# receiver.net
KiCad netlist of a schematic drawn in EAGLE
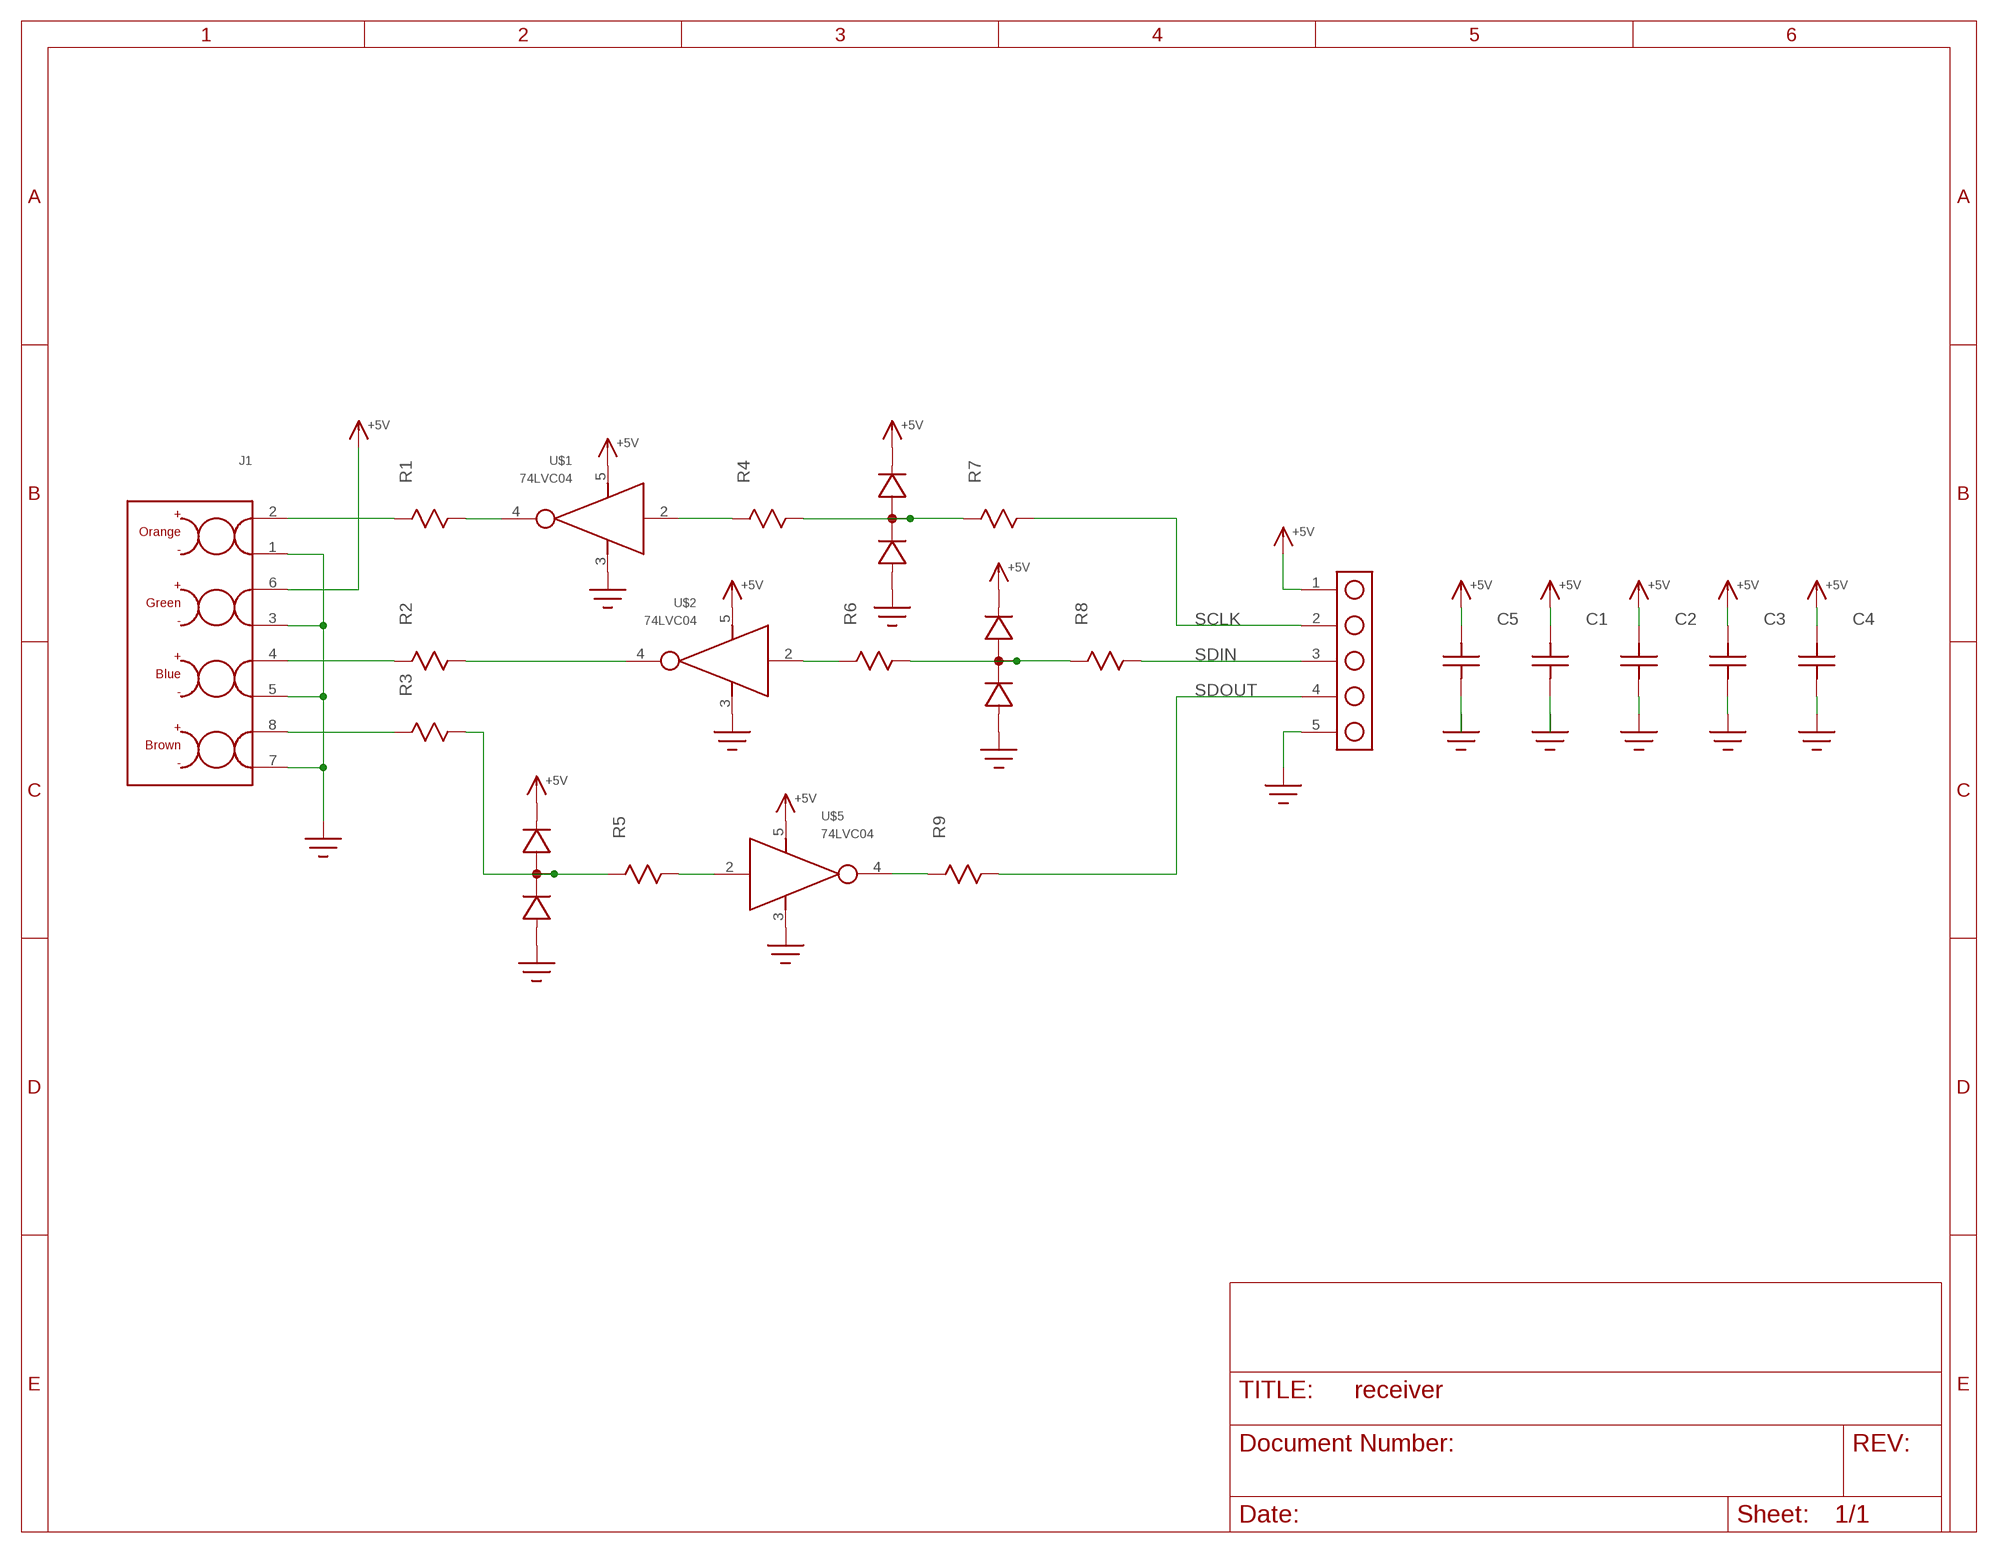
[diagram p0: schematic, sheet 1]

(export (version "E")
  (design (tool "Eeschema 10.0.6"))
  (components
    (comp (ref "C1")
      (value "C1206")
      (footprint "eagle-import:1206")
      (libsource (lib "eagle-import") (part "C1206"))
    )
    (comp (ref "C2")
      (value "C0805")
      (footprint "eagle-import:0805")
      (libsource (lib "eagle-import") (part "C0805"))
    )
    (comp (ref "C3")
      (value "C0805")
      (footprint "eagle-import:0805")
      (libsource (lib "eagle-import") (part "C0805"))
    )
    (comp (ref "C4")
      (value "C0805")
      (footprint "eagle-import:0805")
      (libsource (lib "eagle-import") (part "C0805"))
    )
    (comp (ref "C5")
      (value "C1206")
      (footprint "eagle-import:1206")
      (libsource (lib "eagle-import") (part "C1206"))
    )
    (comp (ref "J1")
      (value "RJ45")
      (footprint "eagle-import:RJ45_KEYSTONE_949")
      (libsource (lib "eagle-import") (part "RJ45"))
    )
    (comp (ref "J2")
      (value "HEADER_5PIN")
      (footprint "eagle-import:HEADER_5PIN")
      (libsource (lib "eagle-import") (part "HEADER_5PIN"))
    )
    (comp (ref "R1")
      (value "R0805")
      (footprint "eagle-import:R0805")
      (libsource (lib "eagle-import") (part "R0805"))
    )
    (comp (ref "R2")
      (value "R0805")
      (footprint "eagle-import:R0805")
      (libsource (lib "eagle-import") (part "R0805"))
    )
    (comp (ref "R3")
      (value "R0805")
      (footprint "eagle-import:R0805")
      (libsource (lib "eagle-import") (part "R0805"))
    )
    (comp (ref "R4")
      (value "R0805")
      (footprint "eagle-import:R0805")
      (libsource (lib "eagle-import") (part "R0805"))
    )
    (comp (ref "R5")
      (value "R0805")
      (footprint "eagle-import:R0805")
      (libsource (lib "eagle-import") (part "R0805"))
    )
    (comp (ref "R6")
      (value "R0805")
      (footprint "eagle-import:R0805")
      (libsource (lib "eagle-import") (part "R0805"))
    )
    (comp (ref "R7")
      (value "R0805")
      (footprint "eagle-import:R0805")
      (libsource (lib "eagle-import") (part "R0805"))
    )
    (comp (ref "R8")
      (value "R0805")
      (footprint "eagle-import:R0805")
      (libsource (lib "eagle-import") (part "R0805"))
    )
    (comp (ref "R9")
      (value "R0805")
      (footprint "eagle-import:R0805")
      (libsource (lib "eagle-import") (part "R0805"))
    )
    (comp (ref "U$1")
      (value "74LVC04")
      (footprint "eagle-import:SOT23-5")
      (libsource (lib "eagle-import") (part "74LVC04"))
    )
    (comp (ref "U$2")
      (value "74LVC04")
      (footprint "eagle-import:SOT23-5")
      (libsource (lib "eagle-import") (part "74LVC04"))
    )
    (comp (ref "U$5")
      (value "74LVC04")
      (footprint "eagle-import:SOT23-5")
      (libsource (lib "eagle-import") (part "74LVC04"))
    )
    (comp (ref "U$12")
      (value "MMBD7000L")
      (footprint "eagle-import:SOT-23")
      (libsource (lib "eagle-import") (part "MMBD7000L"))
    )
    (comp (ref "U$13")
      (value "MMBD7000L")
      (footprint "eagle-import:SOT-23")
      (libsource (lib "eagle-import") (part "MMBD7000L"))
    )
    (comp (ref "U$14")
      (value "MMBD7000L")
      (footprint "eagle-import:SOT-23")
      (libsource (lib "eagle-import") (part "MMBD7000L"))
    )
  )
  (nets
    (net (code "1") (name "+5V") (class "Default")
      (node (ref "C1") (pin "P$2") (pinfunction "P$2_P$2") (pintype "bidirectional"))
      (node (ref "C2") (pin "P$2") (pinfunction "P$2_P$2") (pintype "bidirectional"))
      (node (ref "C3") (pin "P$2") (pinfunction "P$2_P$2") (pintype "bidirectional"))
      (node (ref "C4") (pin "P$2") (pinfunction "P$2_P$2") (pintype "bidirectional"))
      (node (ref "C5") (pin "P$2") (pinfunction "P$2_P$2") (pintype "bidirectional"))
      (node (ref "J1") (pin "6") (pinfunction "6_6") (pintype "bidirectional"))
      (node (ref "J2") (pin "1") (pinfunction "1_1") (pintype "bidirectional"))
      (node (ref "U$1") (pin "5") (pinfunction "VCC_5") (pintype "bidirectional"))
      (node (ref "U$12") (pin "2") (pinfunction "CATHODE_2") (pintype "bidirectional"))
      (node (ref "U$13") (pin "2") (pinfunction "CATHODE_2") (pintype "bidirectional"))
      (node (ref "U$14") (pin "2") (pinfunction "CATHODE_2") (pintype "bidirectional"))
      (node (ref "U$2") (pin "5") (pinfunction "VCC_5") (pintype "bidirectional"))
      (node (ref "U$5") (pin "5") (pinfunction "VCC_5") (pintype "bidirectional"))
    )
    (net (code "2") (name "/SCLK") (class "Default")
      (node (ref "J2") (pin "2") (pinfunction "2_2") (pintype "bidirectional"))
      (node (ref "R7") (pin "P$2") (pinfunction "P$4_P$2") (pintype "bidirectional"))
    )
    (net (code "3") (name "/SDIN") (class "Default")
      (node (ref "J2") (pin "3") (pinfunction "3_3") (pintype "bidirectional"))
      (node (ref "R8") (pin "P$2") (pinfunction "P$4_P$2") (pintype "bidirectional"))
    )
    (net (code "4") (name "/SDOUT") (class "Default")
      (node (ref "J2") (pin "4") (pinfunction "4_4") (pintype "bidirectional"))
      (node (ref "R9") (pin "P$2") (pinfunction "P$4_P$2") (pintype "bidirectional"))
    )
    (net (code "5") (name "GND") (class "Default")
      (node (ref "C1") (pin "P$1") (pinfunction "P$1_P$1") (pintype "bidirectional"))
      (node (ref "C2") (pin "P$1") (pinfunction "P$1_P$1") (pintype "bidirectional"))
      (node (ref "C3") (pin "P$1") (pinfunction "P$1_P$1") (pintype "bidirectional"))
      (node (ref "C4") (pin "P$1") (pinfunction "P$1_P$1") (pintype "bidirectional"))
      (node (ref "C5") (pin "P$1") (pinfunction "P$1_P$1") (pintype "bidirectional"))
      (node (ref "J1") (pin "1") (pinfunction "1_1") (pintype "bidirectional"))
      (node (ref "J1") (pin "3") (pinfunction "3_3") (pintype "bidirectional"))
      (node (ref "J1") (pin "5") (pinfunction "5_5") (pintype "bidirectional"))
      (node (ref "J1") (pin "7") (pinfunction "7_7") (pintype "bidirectional"))
      (node (ref "J2") (pin "5") (pinfunction "5_5") (pintype "bidirectional"))
      (node (ref "U$1") (pin "3") (pinfunction "GND_3") (pintype "bidirectional"))
      (node (ref "U$12") (pin "1") (pinfunction "ANODE_1") (pintype "bidirectional"))
      (node (ref "U$13") (pin "1") (pinfunction "ANODE_1") (pintype "bidirectional"))
      (node (ref "U$14") (pin "1") (pinfunction "ANODE_1") (pintype "bidirectional"))
      (node (ref "U$2") (pin "3") (pinfunction "GND_3") (pintype "bidirectional"))
      (node (ref "U$5") (pin "3") (pinfunction "GND_3") (pintype "bidirectional"))
    )
    (net (code "6") (name "Net-(R1-P$3)") (class "Default")
      (node (ref "J1") (pin "2") (pinfunction "2_2") (pintype "bidirectional"))
      (node (ref "R1") (pin "P$1") (pinfunction "P$3_P$1") (pintype "bidirectional"))
    )
    (net (code "7") (name "Net-(R1-P$4)") (class "Default")
      (node (ref "R1") (pin "P$2") (pinfunction "P$4_P$2") (pintype "bidirectional"))
      (node (ref "U$1") (pin "4") (pinfunction "OUT_4") (pintype "bidirectional"))
    )
    (net (code "8") (name "Net-(R2-P$3)") (class "Default")
      (node (ref "J1") (pin "4") (pinfunction "4_4") (pintype "bidirectional"))
      (node (ref "R2") (pin "P$1") (pinfunction "P$3_P$1") (pintype "bidirectional"))
    )
    (net (code "9") (name "Net-(R2-P$4)") (class "Default")
      (node (ref "R2") (pin "P$2") (pinfunction "P$4_P$2") (pintype "bidirectional"))
      (node (ref "U$2") (pin "4") (pinfunction "OUT_4") (pintype "bidirectional"))
    )
    (net (code "10") (name "Net-(R3-P$3)") (class "Default")
      (node (ref "J1") (pin "8") (pinfunction "8_8") (pintype "bidirectional"))
      (node (ref "R3") (pin "P$1") (pinfunction "P$3_P$1") (pintype "bidirectional"))
    )
    (net (code "11") (name "Net-(R3-P$4)") (class "Default")
      (node (ref "R3") (pin "P$2") (pinfunction "P$4_P$2") (pintype "bidirectional"))
      (node (ref "R5") (pin "P$1") (pinfunction "P$3_P$1") (pintype "bidirectional"))
      (node (ref "U$14") (pin "3") (pinfunction "COMMON_3") (pintype "bidirectional"))
    )
    (net (code "12") (name "Net-(R4-P$3)") (class "Default")
      (node (ref "R4") (pin "P$1") (pinfunction "P$3_P$1") (pintype "bidirectional"))
      (node (ref "U$1") (pin "2") (pinfunction "IN_2") (pintype "bidirectional"))
    )
    (net (code "13") (name "Net-(R4-P$4)") (class "Default")
      (node (ref "R4") (pin "P$2") (pinfunction "P$4_P$2") (pintype "bidirectional"))
      (node (ref "R7") (pin "P$1") (pinfunction "P$3_P$1") (pintype "bidirectional"))
      (node (ref "U$12") (pin "3") (pinfunction "COMMON_3") (pintype "bidirectional"))
    )
    (net (code "14") (name "Net-(R5-P$4)") (class "Default")
      (node (ref "R5") (pin "P$2") (pinfunction "P$4_P$2") (pintype "bidirectional"))
      (node (ref "U$5") (pin "2") (pinfunction "IN_2") (pintype "bidirectional"))
    )
    (net (code "15") (name "Net-(R6-P$3)") (class "Default")
      (node (ref "R6") (pin "P$1") (pinfunction "P$3_P$1") (pintype "bidirectional"))
      (node (ref "U$2") (pin "2") (pinfunction "IN_2") (pintype "bidirectional"))
    )
    (net (code "16") (name "Net-(R6-P$4)") (class "Default")
      (node (ref "R6") (pin "P$2") (pinfunction "P$4_P$2") (pintype "bidirectional"))
      (node (ref "R8") (pin "P$1") (pinfunction "P$3_P$1") (pintype "bidirectional"))
      (node (ref "U$13") (pin "3") (pinfunction "COMMON_3") (pintype "bidirectional"))
    )
    (net (code "17") (name "Net-(R9-P$3)") (class "Default")
      (node (ref "R9") (pin "P$1") (pinfunction "P$3_P$1") (pintype "bidirectional"))
      (node (ref "U$5") (pin "4") (pinfunction "OUT_4") (pintype "bidirectional"))
    )
  )
)
